# Asfaloth_L2_AVI_ver1_1.net
KiCad netlist of a schematic drawn in Altium Designer
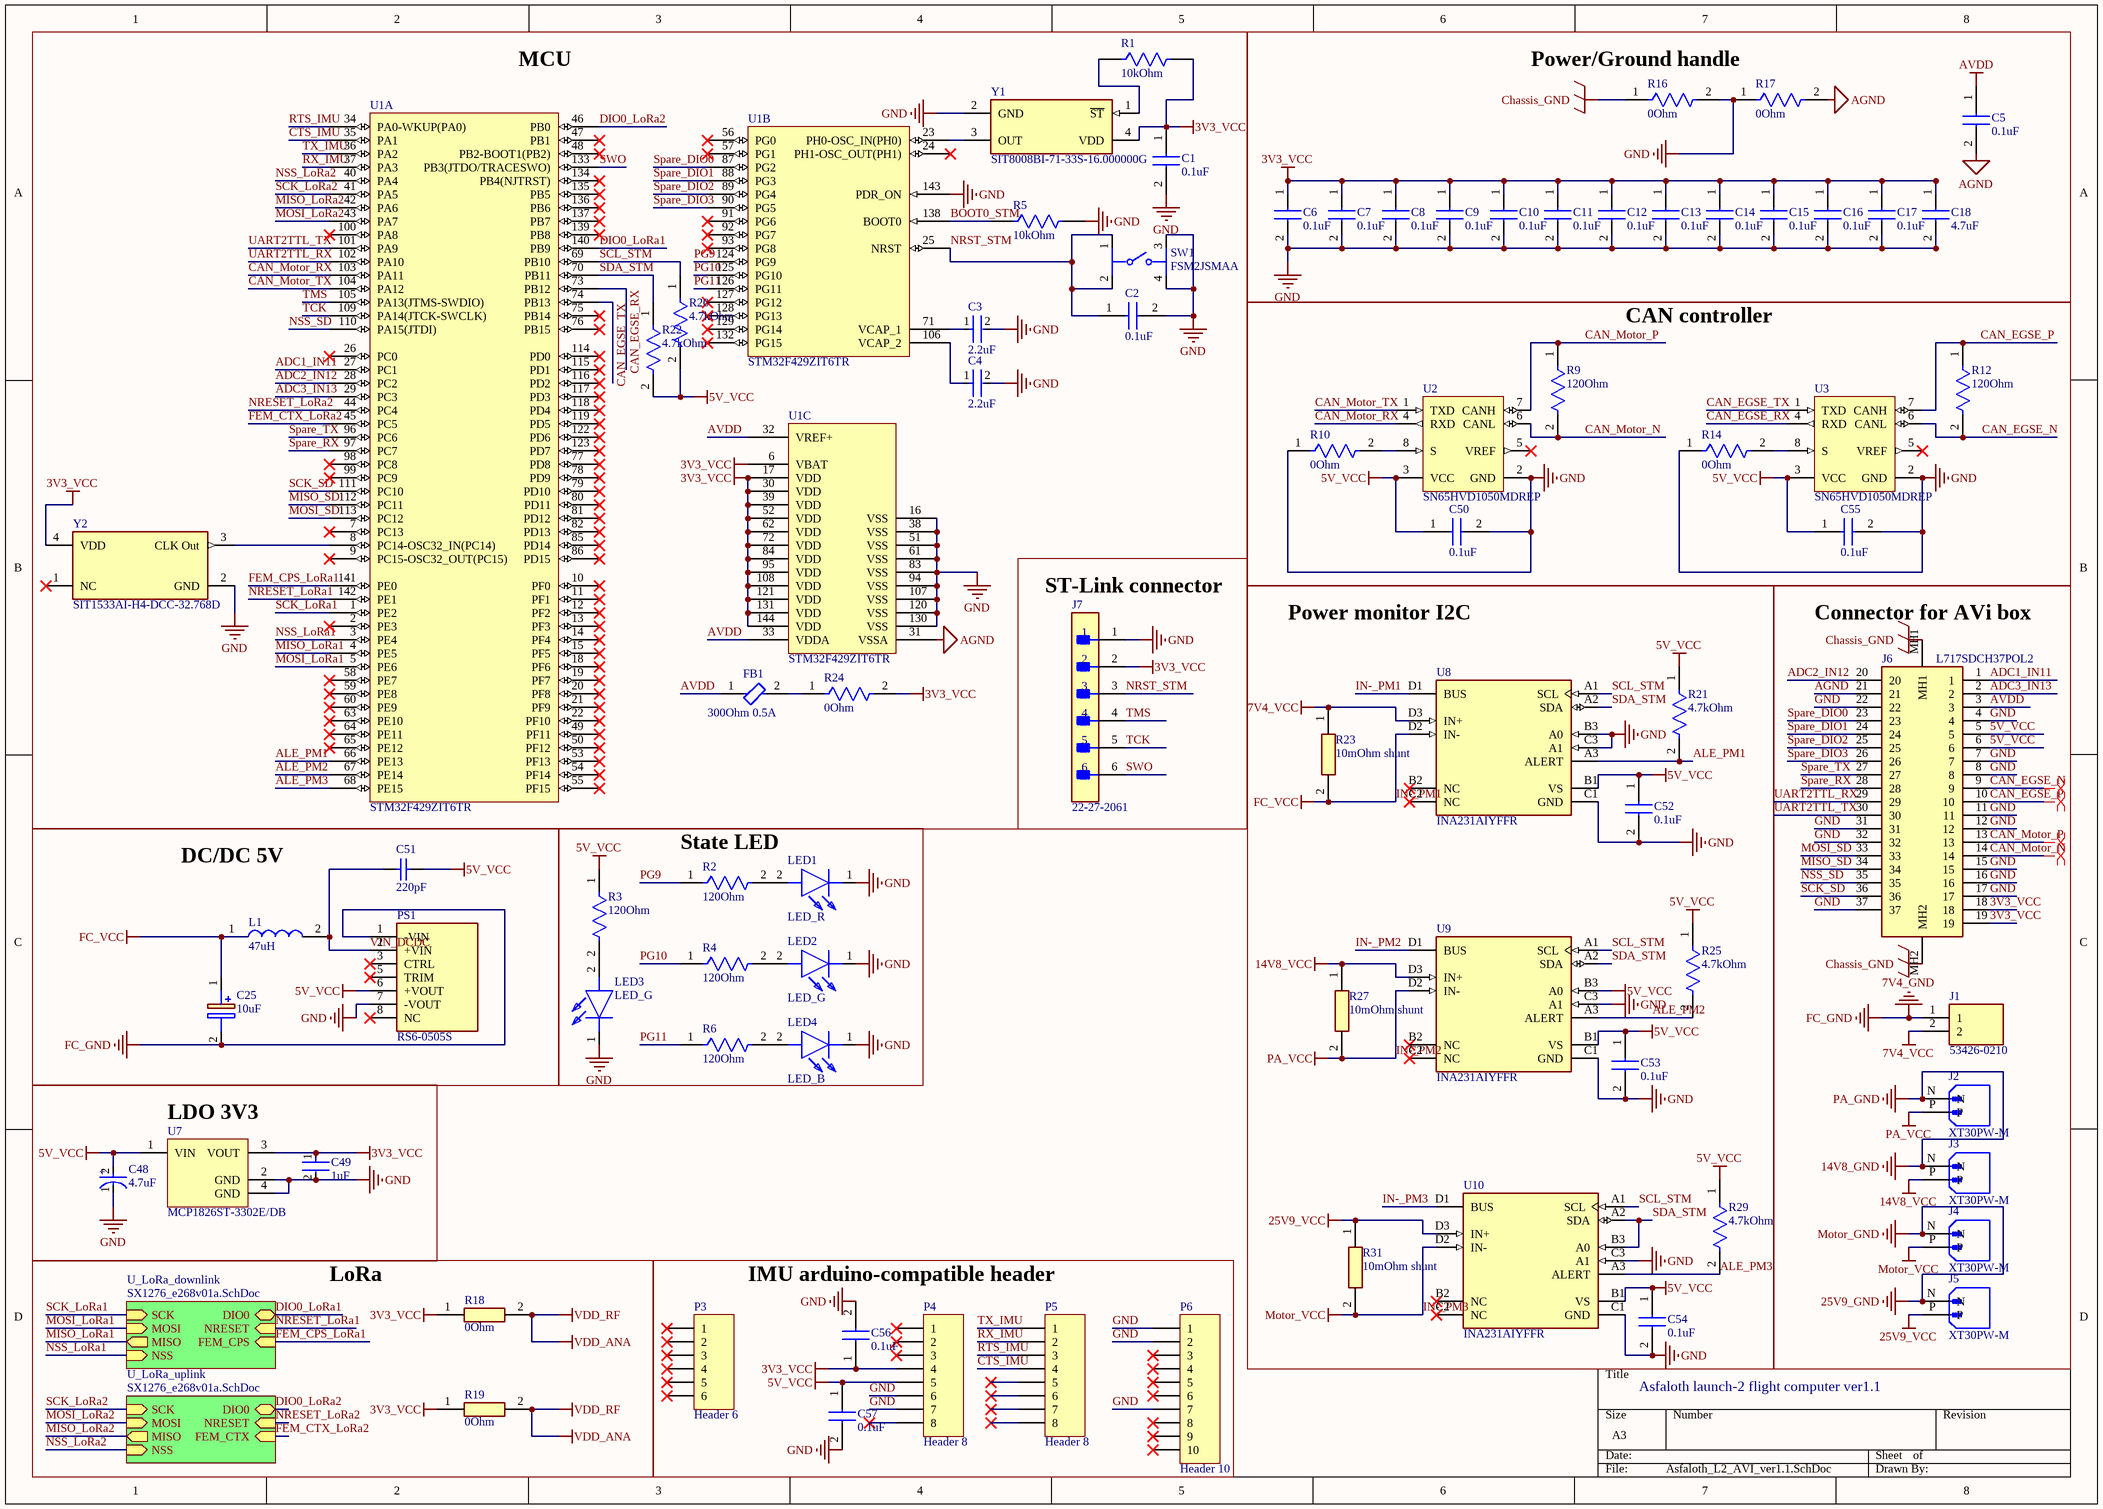
[diagram p0: Asfaloth_L2_AVI_ver1.1.SchDoc]

(export (version "E")
  (design (tool "Eeschema 10.0.6"))
  (components
    (comp (ref "C1")
      (value "0.1uF")
      (footprint "SamacSys:CAPC1608X87N")
      (description "Capacitor")
      (fields
        (field (name "MANUFACTURER_PART_NUMBER") "C0603C104J4RECAUTO")
        (field (name "MOUSER PART NUMBER") "80-C0603C104J4RECAUT")
      )
      (libsource (lib "*") (part "C0603C104J4RECAUTO"))
    )
    (comp (ref "C2")
      (value "0.1uF")
      (footprint "SamacSys:CAPC1608X87N")
      (description "Capacitor")
      (fields
        (field (name "MANUFACTURER_PART_NUMBER") "C0603C104J4RECAUTO")
        (field (name "MOUSER PART NUMBER") "80-C0603C104J4RECAUT")
      )
      (libsource (lib "*") (part "C0603C104J4RECAUTO"))
    )
    (comp (ref "C3")
      (value "2.2uF")
      (footprint "FP-GRT155-0_2-IPC_C")
      (description "Multi-Layer Ceramic Capacitor 2.2uF 10V X6S ±10% 0402 Paper T/R")
      (fields (field (name "TOLERANCE") "10%"))
      (libsource (lib "Altium Content Vault") (part "02cd4be3c70576c341d710602a673aa"))
    )
    (comp (ref "C4")
      (value "2.2uF")
      (footprint "FP-GRT155-0_2-IPC_C")
      (description "Multi-Layer Ceramic Capacitor 2.2uF 10V X6S ±10% 0402 Paper T/R")
      (fields (field (name "TOLERANCE") "10%"))
      (libsource (lib "Altium Content Vault") (part "02cd4be3c70576c341d710602a673aa"))
    )
    (comp (ref "C5")
      (value "0.1uF")
      (footprint "SamacSys:CAPC1608X87N")
      (description "Capacitor")
      (fields
        (field (name "MANUFACTURER_PART_NUMBER") "C0603C104J4RECAUTO")
        (field (name "MOUSER PART NUMBER") "80-C0603C104J4RECAUT")
      )
      (libsource (lib "*") (part "C0603C104J4RECAUTO"))
    )
    (comp (ref "C6")
      (value "0.1uF")
      (footprint "SamacSys:CAPC1608X87N")
      (description "Capacitor")
      (fields
        (field (name "MANUFACTURER_PART_NUMBER") "C0603C104J4RECAUTO")
        (field (name "MOUSER PART NUMBER") "80-C0603C104J4RECAUT")
      )
      (libsource (lib "*") (part "C0603C104J4RECAUTO"))
    )
    (comp (ref "C7")
      (value "0.1uF")
      (footprint "SamacSys:CAPC1608X87N")
      (description "Capacitor")
      (fields
        (field (name "MANUFACTURER_PART_NUMBER") "C0603C104J4RECAUTO")
        (field (name "MOUSER PART NUMBER") "80-C0603C104J4RECAUT")
      )
      (libsource (lib "*") (part "C0603C104J4RECAUTO"))
    )
    (comp (ref "C8")
      (value "0.1uF")
      (footprint "SamacSys:CAPC1608X87N")
      (description "Capacitor")
      (fields
        (field (name "MANUFACTURER_PART_NUMBER") "C0603C104J4RECAUTO")
        (field (name "MOUSER PART NUMBER") "80-C0603C104J4RECAUT")
      )
      (libsource (lib "*") (part "C0603C104J4RECAUTO"))
    )
    (comp (ref "C9")
      (value "0.1uF")
      (footprint "SamacSys:CAPC1608X87N")
      (description "Capacitor")
      (fields
        (field (name "MANUFACTURER_PART_NUMBER") "C0603C104J4RECAUTO")
        (field (name "MOUSER PART NUMBER") "80-C0603C104J4RECAUT")
      )
      (libsource (lib "*") (part "C0603C104J4RECAUTO"))
    )
    (comp (ref "C10")
      (value "0.1uF")
      (footprint "SamacSys:CAPC1608X87N")
      (description "Capacitor")
      (fields
        (field (name "MANUFACTURER_PART_NUMBER") "C0603C104J4RECAUTO")
        (field (name "MOUSER PART NUMBER") "80-C0603C104J4RECAUT")
      )
      (libsource (lib "*") (part "C0603C104J4RECAUTO"))
    )
    (comp (ref "C11")
      (value "0.1uF")
      (footprint "SamacSys:CAPC1608X87N")
      (description "Capacitor")
      (fields
        (field (name "MANUFACTURER_PART_NUMBER") "C0603C104J4RECAUTO")
        (field (name "MOUSER PART NUMBER") "80-C0603C104J4RECAUT")
      )
      (libsource (lib "*") (part "C0603C104J4RECAUTO"))
    )
    (comp (ref "C12")
      (value "0.1uF")
      (footprint "SamacSys:CAPC1608X87N")
      (description "Capacitor")
      (fields
        (field (name "MANUFACTURER_PART_NUMBER") "C0603C104J4RECAUTO")
        (field (name "MOUSER PART NUMBER") "80-C0603C104J4RECAUT")
      )
      (libsource (lib "*") (part "C0603C104J4RECAUTO"))
    )
    (comp (ref "C13")
      (value "0.1uF")
      (footprint "SamacSys:CAPC1608X87N")
      (description "Capacitor")
      (fields
        (field (name "MANUFACTURER_PART_NUMBER") "C0603C104J4RECAUTO")
        (field (name "MOUSER PART NUMBER") "80-C0603C104J4RECAUT")
      )
      (libsource (lib "*") (part "C0603C104J4RECAUTO"))
    )
    (comp (ref "C14")
      (value "0.1uF")
      (footprint "SamacSys:CAPC1608X87N")
      (description "Capacitor")
      (fields
        (field (name "MANUFACTURER_PART_NUMBER") "C0603C104J4RECAUTO")
        (field (name "MOUSER PART NUMBER") "80-C0603C104J4RECAUT")
      )
      (libsource (lib "*") (part "C0603C104J4RECAUTO"))
    )
    (comp (ref "C15")
      (value "0.1uF")
      (footprint "SamacSys:CAPC1608X87N")
      (description "Capacitor")
      (fields
        (field (name "MANUFACTURER_PART_NUMBER") "C0603C104J4RECAUTO")
        (field (name "MOUSER PART NUMBER") "80-C0603C104J4RECAUT")
      )
      (libsource (lib "*") (part "C0603C104J4RECAUTO"))
    )
    (comp (ref "C16")
      (value "0.1uF")
      (footprint "SamacSys:CAPC1608X87N")
      (description "Capacitor")
      (fields
        (field (name "MANUFACTURER_PART_NUMBER") "C0603C104J4RECAUTO")
        (field (name "MOUSER PART NUMBER") "80-C0603C104J4RECAUT")
      )
      (libsource (lib "*") (part "C0603C104J4RECAUTO"))
    )
    (comp (ref "C17")
      (value "0.1uF")
      (footprint "SamacSys:CAPC1608X87N")
      (description "Capacitor")
      (fields
        (field (name "MANUFACTURER_PART_NUMBER") "C0603C104J4RECAUTO")
        (field (name "MOUSER PART NUMBER") "80-C0603C104J4RECAUT")
      )
      (libsource (lib "*") (part "C0603C104J4RECAUTO"))
    )
    (comp (ref "C18")
      (value "4.7uF")
      (footprint "SamacSys:GRT188")
      (description "Capacitor")
      (fields
        (field (name "MANUFACTURER_PART_NUMBER") "GRT188C71C475KE13D")
        (field (name "MOUSER PART NUMBER") "81-GRT188C71C475KE13")
      )
      (libsource (lib "*") (part "GRT188C71C475KE13D"))
    )
    (comp (ref "C25")
      (value "10uF")
      (footprint "SamacSys:CAPAE830X650N")
      (description "Capacitor Polarised")
      (fields
        (field (name "MANUFACTURER_PART_NUMBER") "EEE-TG1J100P")
        (field (name "MOUSER PART NUMBER") "667-EEE-TG1J100P")
      )
      (libsource (lib "*") (part "EEE-TG1J100P"))
    )
    (comp (ref "C48")
      (value "4.7uF")
      (footprint "FP-TAJA-MFG")
      (description "4.7uF 16V  ±10% 4Ω 1206  SMD Tantalum Capacitor")
      (fields (field (name "TOLERANCE") "10%") (field (name "VOLTAGE") "16V"))
      (libsource (lib "Altium Content Vault") (part "203bc49f2ac43e59fd269a8c329ed05"))
    )
    (comp (ref "C49")
      (value "1uF")
      (footprint "FP-GCM21B-0_15-MFG")
      (description "Ceramic Capacitor for Automotive 1uF ±10% 16VDC X7R 0805 Embossed T/R")
      (fields (field (name "TOLERANCE") "10%"))
      (libsource (lib "Altium Content Vault") (part "02cd4be3c70576c341d710602a673aa"))
    )
    (comp (ref "C50")
      (value "0.1uF")
      (footprint "SamacSys:CAPC1608X87N")
      (description "Capacitor")
      (fields
        (field (name "MANUFACTURER_PART_NUMBER") "C0603C104J4RECAUTO")
        (field (name "MOUSER PART NUMBER") "80-C0603C104J4RECAUT")
      )
      (libsource (lib "*") (part "C0603C104J4RECAUTO"))
    )
    (comp (ref "C51")
      (value "220pF")
      (footprint "CAPC1608X87X35LL15T15")
      (fields (field (name "PART NUMBER") "C0603C221J5GACAUTO") (field (name "MANUFACTURER") "Kemet"))
      (libsource (lib "Altium Content Vault") (part "CAP"))
    )
    (comp (ref "C52")
      (value "0.1uF")
      (footprint "SamacSys:CAPC1608X87N")
      (description "Capacitor")
      (fields
        (field (name "MANUFACTURER_PART_NUMBER") "C0603C104J4RECAUTO")
        (field (name "MOUSER PART NUMBER") "80-C0603C104J4RECAUT")
      )
      (libsource (lib "*") (part "C0603C104J4RECAUTO"))
    )
    (comp (ref "C53")
      (value "0.1uF")
      (footprint "SamacSys:CAPC1608X87N")
      (description "Capacitor")
      (fields
        (field (name "MANUFACTURER_PART_NUMBER") "C0603C104J4RECAUTO")
        (field (name "MOUSER PART NUMBER") "80-C0603C104J4RECAUT")
      )
      (libsource (lib "*") (part "C0603C104J4RECAUTO"))
    )
    (comp (ref "C54")
      (value "0.1uF")
      (footprint "SamacSys:CAPC1608X87N")
      (description "Capacitor")
      (fields
        (field (name "MANUFACTURER_PART_NUMBER") "C0603C104J4RECAUTO")
        (field (name "MOUSER PART NUMBER") "80-C0603C104J4RECAUT")
      )
      (libsource (lib "*") (part "C0603C104J4RECAUTO"))
    )
    (comp (ref "C55")
      (value "0.1uF")
      (footprint "SamacSys:CAPC1608X87N")
      (description "Capacitor")
      (fields
        (field (name "MANUFACTURER_PART_NUMBER") "C0603C104J4RECAUTO")
        (field (name "MOUSER PART NUMBER") "80-C0603C104J4RECAUT")
      )
      (libsource (lib "*") (part "C0603C104J4RECAUTO"))
    )
    (comp (ref "C56")
      (value "0.1uF")
      (footprint "SamacSys:CAPC1608X87N")
      (description "Capacitor")
      (fields
        (field (name "MANUFACTURER_PART_NUMBER") "C0603C104J4RECAUTO")
        (field (name "MOUSER PART NUMBER") "80-C0603C104J4RECAUT")
      )
      (libsource (lib "*") (part "C0603C104J4RECAUTO"))
    )
    (comp (ref "C57")
      (value "0.1uF")
      (footprint "SamacSys:CAPC1608X87N")
      (description "Capacitor")
      (fields
        (field (name "MANUFACTURER_PART_NUMBER") "C0603C104J4RECAUTO")
        (field (name "MOUSER PART NUMBER") "80-C0603C104J4RECAUT")
      )
      (libsource (lib "*") (part "C0603C104J4RECAUTO"))
    )
    (comp (ref "FB1")
      (value "300Ohm 0.5A")
      (footprint "FP-MMZ1608-0_8-MFG")
      (description " Signal Line Ferrite Bead 300Ω  @ 100MHz 500mA DCR 300mΩ SMD 0603")
      (fields (field (name "TOLERANCE") "25%"))
      (libsource (lib "Altium Content Vault") (part "5f30dd21d616792df468990f7003faa"))
    )
    (comp (ref "J1")
      (value "53426-0210")
      (footprint "534260210")
      (description "Headers & Wire Housings 2.50MM 2P RA HDR FRCTN POS LOCK")
      (fields (field (name "MOUSER PART NUMBER") "538-53426-0210"))
      (libsource (lib "53426-0210") (part "53426-0210"))
    )
    (comp (ref "J2")
      (value "XT30PW-M")
      (footprint "AMASS_XT30PW-M")
      (description "Socket; DC supply; XT30; male; PIN: 2; on PCBs; THT; Colour: yellow")
      (fields (field (name "MF") "AMASS"))
      (libsource (lib "XT30PW-M") (part "XT30PW-M"))
    )
    (comp (ref "J3")
      (value "XT30PW-M")
      (footprint "AMASS_XT30PW-M")
      (description "Socket; DC supply; XT30; male; PIN: 2; on PCBs; THT; Colour: yellow")
      (fields (field (name "MF") "AMASS"))
      (libsource (lib "XT30PW-M") (part "XT30PW-M"))
    )
    (comp (ref "J4")
      (value "XT30PW-M")
      (footprint "AMASS_XT30PW-M")
      (description "Socket; DC supply; XT30; male; PIN: 2; on PCBs; THT; Colour: yellow")
      (fields (field (name "MF") "AMASS"))
      (libsource (lib "XT30PW-M") (part "XT30PW-M"))
    )
    (comp (ref "J5")
      (value "XT30PW-M")
      (footprint "AMASS_XT30PW-M")
      (description "Socket; DC supply; XT30; male; PIN: 2; on PCBs; THT; Colour: yellow")
      (fields (field (name "MF") "AMASS"))
      (libsource (lib "XT30PW-M") (part "XT30PW-M"))
    )
    (comp (ref "J6")
      (value "L717SDCH37POL2")
      (footprint "L717SDCH37POL2")
      (libsource (lib "L717SDCH37POL2") (part "L717SDCH37POL2"))
    )
    (comp (ref "J7")
      (value "22-27-2061")
      (footprint "FP-22-27-2061-MFG")
      (description "CONN HEADER VERT 6POS 2.54MM")
      (libsource (lib "Altium Content Vault") (part "f2cb566baf1c37ab5a3b8e90bbeafd6"))
    )
    (comp (ref "L1")
      (value "47uH")
      (footprint "SamacSys:SRR5228A")
      (description "Inductor")
      (fields
        (field (name "MANUFACTURER_PART_NUMBER") "SRR5228A-470M")
        (field (name "MOUSER PART NUMBER") "6521-SRR5228A-470M")
      )
      (libsource (lib "*") (part "SRR5228A-470M"))
    )
    (comp (ref "LED1")
      (value "LED_R")
      (footprint "SamacSys:LEDC2012X80N")
      (description "LED")
      (fields
        (field (name "MANUFACTURER_PART_NUMBER") "SML-H12V8TT86C")
        (field (name "MOUSER PART NUMBER") "755-SML-H12V8TT86C")
      )
      (libsource (lib "*") (part "SML-H12V8TT86C"))
    )
    (comp (ref "LED2")
      (value "LED_G")
      (footprint "SamacSys:LEDC2012X90N")
      (description "LED")
      (fields
        (field (name "MANUFACTURER_PART_NUMBER") "SML-H12P8TT86C")
        (field (name "MOUSER PART NUMBER") "755-SML-H12P8TT86C")
      )
      (libsource (lib "*") (part "SML-H12P8TT86C"))
    )
    (comp (ref "LED3")
      (value "LED_G")
      (footprint "SamacSys:LEDC2012X90N")
      (description "LED")
      (fields
        (field (name "MANUFACTURER_PART_NUMBER") "SML-H12P8TT86C")
        (field (name "MOUSER PART NUMBER") "755-SML-H12P8TT86C")
      )
      (libsource (lib "*") (part "SML-H12P8TT86C"))
    )
    (comp (ref "LED4")
      (value "LED_B")
      (footprint "SamacSys:LEDM2012X100N")
      (description "LED")
      (fields
        (field (name "MANUFACTURER_PART_NUMBER") "SMLMN2BCTT86C")
        (field (name "MOUSER PART NUMBER") "755-SMLMN2BCTT86C")
      )
      (libsource (lib "*") (part "SMLMN2BCTT86C"))
    )
    (comp (ref "P3")
      (value "Header 6")
      (footprint "HDR1X6")
      (description "Header, 6-Pin")
      (fields (field (name "PUBLISHER") "Altium Limited"))
      (libsource (lib "Miscellaneous Connectors") (part "Header 6"))
    )
    (comp (ref "P4")
      (value "Header 8")
      (footprint "HDR1X8")
      (description "Header, 8-Pin")
      (fields (field (name "PUBLISHER") "Altium Limited"))
      (libsource (lib "Miscellaneous Connectors") (part "Header 8"))
    )
    (comp (ref "P5")
      (value "Header 8")
      (footprint "HDR1X8")
      (description "Header, 8-Pin")
      (fields (field (name "PUBLISHER") "Altium Limited"))
      (libsource (lib "Miscellaneous Connectors") (part "Header 8"))
    )
    (comp (ref "P6")
      (value "Header 10")
      (footprint "HDR1X10")
      (description "Header, 10-Pin")
      (fields (field (name "PUBLISHER") "Altium Limited"))
      (libsource (lib "Miscellaneous Connectors") (part "Header 10"))
    )
    (comp (ref "PS1")
      (value "RS6-0505S")
      (footprint "SamacSys:RS60505S")
      (description "Power Supply")
      (fields (field (name "MOUSER PART NUMBER") "919-RS6-0505S"))
      (libsource (lib "*") (part "RS6-0505S"))
    )
    (comp (ref "R1")
      (value "10kOhm")
      (footprint "FP-CRCW0805-e3-IPC_A")
      (description "RES Thick Film, 10kΩ, 1%, 0.125W, 100ppm/°C, 0805")
      (fields (field (name "TOLERANCE") "1%"))
      (libsource (lib "") (part "1029c3af85768c4190bb7ad29bc67b5_1"))
    )
    (comp (ref "R2")
      (value "120Ohm")
      (footprint "FP-ERJ2RK-MFG")
      (description "RES SMD 120 OHM 1% 1/10W 0402")
      (fields (field (name "TOLERANCE") "1%"))
      (libsource (lib "Altium Content Vault") (part "1029c3af85768c4190bb7ad29bc67b5"))
    )
    (comp (ref "R3")
      (value "120Ohm")
      (footprint "FP-ERJ2RK-MFG")
      (description "RES SMD 120 OHM 1% 1/10W 0402")
      (fields (field (name "TOLERANCE") "1%"))
      (libsource (lib "Altium Content Vault") (part "1029c3af85768c4190bb7ad29bc67b5"))
    )
    (comp (ref "R4")
      (value "120Ohm")
      (footprint "FP-ERJ2RK-MFG")
      (description "RES SMD 120 OHM 1% 1/10W 0402")
      (fields (field (name "TOLERANCE") "1%"))
      (libsource (lib "Altium Content Vault") (part "1029c3af85768c4190bb7ad29bc67b5"))
    )
    (comp (ref "R5")
      (value "10kOhm")
      (footprint "FP-CRCW0805-e3-IPC_A")
      (description "RES Thick Film, 10kΩ, 1%, 0.125W, 100ppm/°C, 0805")
      (fields (field (name "TOLERANCE") "1%"))
      (libsource (lib "") (part "1029c3af85768c4190bb7ad29bc67b5_1"))
    )
    (comp (ref "R6")
      (value "120Ohm")
      (footprint "FP-ERJ2RK-MFG")
      (description "RES SMD 120 OHM 1% 1/10W 0402")
      (fields (field (name "TOLERANCE") "1%"))
      (libsource (lib "Altium Content Vault") (part "1029c3af85768c4190bb7ad29bc67b5"))
    )
    (comp (ref "R9")
      (value "120Ohm")
      (footprint "FP-ERJ2RK-MFG")
      (description "RES SMD 120 OHM 1% 1/10W 0402")
      (fields (field (name "TOLERANCE") "1%"))
      (libsource (lib "Altium Content Vault") (part "1029c3af85768c4190bb7ad29bc67b5"))
    )
    (comp (ref "R10")
      (value "0Ohm")
      (footprint "FP-AC0603-0_55-IPC_A")
      (description "RES SMD 0 OHM JUMPER 1/10W 0603")
      (fields (field (name "TOLERANCE") "1%"))
      (libsource (lib "Altium Content Vault") (part "1029c3af85768c4190bb7ad29bc67b5"))
    )
    (comp (ref "R12")
      (value "120Ohm")
      (footprint "FP-ERJ2RK-MFG")
      (description "RES SMD 120 OHM 1% 1/10W 0402")
      (fields (field (name "TOLERANCE") "1%"))
      (libsource (lib "Altium Content Vault") (part "1029c3af85768c4190bb7ad29bc67b5"))
    )
    (comp (ref "R14")
      (value "0Ohm")
      (footprint "FP-AC0603-0_55-IPC_A")
      (description "RES SMD 0 OHM JUMPER 1/10W 0603")
      (fields (field (name "TOLERANCE") "1%"))
      (libsource (lib "Altium Content Vault") (part "1029c3af85768c4190bb7ad29bc67b5"))
    )
    (comp (ref "R16")
      (value "0Ohm")
      (footprint "FP-AC0603-0_55-IPC_A")
      (description "RES SMD 0 OHM JUMPER 1/10W 0603")
      (fields (field (name "TOLERANCE") "1%"))
      (libsource (lib "Altium Content Vault") (part "1029c3af85768c4190bb7ad29bc67b5"))
    )
    (comp (ref "R17")
      (value "0Ohm")
      (footprint "FP-AC0603-0_55-IPC_A")
      (description "RES SMD 0 OHM JUMPER 1/10W 0603")
      (fields (field (name "TOLERANCE") "1%"))
      (libsource (lib "Altium Content Vault") (part "1029c3af85768c4190bb7ad29bc67b5"))
    )
    (comp (ref "R18")
      (value "0Ohm")
      (footprint "SamacSys:RESC3216X60N")
      (description "Resistor")
      (fields
        (field (name "MANUFACTURER_PART_NUMBER") "RCA12060000ZSEA")
        (field (name "MOUSER PART NUMBER") "71-RCA12060000ZSEA")
      )
      (libsource (lib "*") (part "RCA12060000ZSEA"))
    )
    (comp (ref "R19")
      (value "0Ohm")
      (footprint "SamacSys:RESC3216X60N")
      (description "Resistor")
      (fields
        (field (name "MANUFACTURER_PART_NUMBER") "RCA12060000ZSEA")
        (field (name "MOUSER PART NUMBER") "71-RCA12060000ZSEA")
      )
      (libsource (lib "*") (part "RCA12060000ZSEA"))
    )
    (comp (ref "R20")
      (value "4.7kOhm")
      (footprint "FP-KTR03-IPC_C")
      (description "Res Thick Film 0603 4.7kΩ 5% 0.1W ±200ppm/°C Automotive Paper T/R")
      (fields (field (name "TOLERANCE") "5%"))
      (libsource (lib "Altium Content Vault") (part "1029c3af85768c4190bb7ad29bc67b5"))
    )
    (comp (ref "R21")
      (value "4.7kOhm")
      (footprint "FP-KTR03-IPC_C")
      (description "Res Thick Film 0603 4.7kΩ 5% 0.1W ±200ppm/°C Automotive Paper T/R")
      (fields (field (name "TOLERANCE") "5%"))
      (libsource (lib "Altium Content Vault") (part "1029c3af85768c4190bb7ad29bc67b5"))
    )
    (comp (ref "R22")
      (value "4.7kOhm")
      (footprint "FP-KTR03-IPC_C")
      (description "Res Thick Film 0603 4.7kΩ 5% 0.1W ±200ppm/°C Automotive Paper T/R")
      (fields (field (name "TOLERANCE") "5%"))
      (libsource (lib "Altium Content Vault") (part "1029c3af85768c4190bb7ad29bc67b5"))
    )
    (comp (ref "R23")
      (value "10mOhm shunt")
      (footprint "SamacSys:CSS0805FT10L0")
      (description "Resistor")
      (fields
        (field (name "MANUFACTURER_PART_NUMBER") "CSS0805FT10L0")
        (field (name "MOUSER PART NUMBER") "708-CSS0805FT10L0")
      )
      (libsource (lib "*") (part "CSS0805FT10L0"))
    )
    (comp (ref "R24")
      (value "0Ohm")
      (footprint "FP-AC0603-0_55-IPC_A")
      (description "RES SMD 0 OHM JUMPER 1/10W 0603")
      (fields (field (name "TOLERANCE") "1%"))
      (libsource (lib "Altium Content Vault") (part "1029c3af85768c4190bb7ad29bc67b5"))
    )
    (comp (ref "R25")
      (value "4.7kOhm")
      (footprint "FP-KTR03-IPC_C")
      (description "Res Thick Film 0603 4.7kΩ 5% 0.1W ±200ppm/°C Automotive Paper T/R")
      (fields (field (name "TOLERANCE") "5%"))
      (libsource (lib "Altium Content Vault") (part "1029c3af85768c4190bb7ad29bc67b5"))
    )
    (comp (ref "R27")
      (value "10mOhm shunt")
      (footprint "SamacSys:CSS0805FT10L0")
      (description "Resistor")
      (fields
        (field (name "MANUFACTURER_PART_NUMBER") "CSS0805FT10L0")
        (field (name "MOUSER PART NUMBER") "708-CSS0805FT10L0")
      )
      (libsource (lib "*") (part "CSS0805FT10L0"))
    )
    (comp (ref "R29")
      (value "4.7kOhm")
      (footprint "FP-KTR03-IPC_C")
      (description "Res Thick Film 0603 4.7kΩ 5% 0.1W ±200ppm/°C Automotive Paper T/R")
      (fields (field (name "TOLERANCE") "5%"))
      (libsource (lib "Altium Content Vault") (part "1029c3af85768c4190bb7ad29bc67b5"))
    )
    (comp (ref "R31")
      (value "10mOhm shunt")
      (footprint "SamacSys:CSS0805FT10L0")
      (description "Resistor")
      (fields
        (field (name "MANUFACTURER_PART_NUMBER") "CSS0805FT10L0")
        (field (name "MOUSER PART NUMBER") "708-CSS0805FT10L0")
      )
      (libsource (lib "*") (part "CSS0805FT10L0"))
    )
    (comp (ref "SW1")
      (value "FSM2JSMAA")
      (footprint "FP-FSM2JSMAA-MFG")
      (description "SWITCH TACTILE SPST-NO 0.05A 24V")
      (fields
        (field (name "MANUFACTURER") "TE Connectivity")
        (field (name "OCTOPART") "https://octopart.com/fsm2jsmaa-te+connectivity-41720620")
      )
      (libsource (lib "Altium Content Vault") (part "b8895f3f4cefb76e1819d2863dba89b"))
    )
    (comp (ref "U1")
      (value "STM32F429ZIT6TR")
      (footprint "STM-LQFP144_M")
      (libsource (lib "Altium Content Vault") (part "MC-ARM-STM32F4X7_9-LQFP144"))
    )
    (comp (ref "U2")
      (value "SN65HVD1050MDREP")
      (footprint "D0008A_M")
      (fields (field (name "MANUFACTURER") "Texas Instruments"))
      (libsource (lib "Altium Content Vault") (part "TI-SN65HVD1050-EP-SOIC_D-8"))
    )
    (comp (ref "U3")
      (value "SN65HVD1050MDREP")
      (footprint "D0008A_M")
      (fields (field (name "MANUFACTURER") "Texas Instruments"))
      (libsource (lib "Altium Content Vault") (part "TI-SN65HVD1050-EP-SOIC_D-8"))
    )
    (comp (ref "U7")
      (value "MCP1826ST-3302E/DB")
      (footprint "SOT-223-DB3_L")
      (libsource (lib "Altium Content Vault") (part "PM-LINEREG-MCP1826-IL4"))
    )
    (comp (ref "U8")
      (value "INA231AIYFFR")
      (footprint "FP-YFF0012-IPC_C")
      (description "IC CURRENT MONITOR 100DB 12DSBGA")
      (libsource (lib "Altium Content Vault") (part "45ec0a68ca5e232ea1aa11670bcc384"))
    )
    (comp (ref "U9")
      (value "INA231AIYFFR")
      (footprint "FP-YFF0012-IPC_C")
      (description "IC CURRENT MONITOR 100DB 12DSBGA")
      (libsource (lib "Altium Content Vault") (part "45ec0a68ca5e232ea1aa11670bcc384"))
    )
    (comp (ref "U10")
      (value "INA231AIYFFR")
      (footprint "FP-YFF0012-IPC_C")
      (description "IC CURRENT MONITOR 100DB 12DSBGA")
      (libsource (lib "Altium Content Vault") (part "45ec0a68ca5e232ea1aa11670bcc384"))
    )
    (comp (ref "Y1")
      (value "SIT8008BI-71-33S-16.000000G")
      (footprint "FP-SiT8008-7-MFG")
      (description "MEMS OSC XO 16.0000MHZ H/LV-CMOS")
      (libsource (lib "Altium Content Vault") (part "0b6e30c8c84b5cf713c4e00c700effb"))
    )
    (comp (ref "Y2")
      (value "SIT1533AI-H4-DCC-32.768D")
      (footprint "FP-SiT1533-H-MFG")
      (description "MEMS OSC XO 32.7680KHZ LVCMOS")
      (libsource (lib "Altium Content Vault") (part "d6da4f2ecb1e1a500d17fb349569450"))
    )
  )
  (nets
    (net (code "1") (name "/ADC1_IN11") (class "Default")
      (node (ref "J6") (pin "1") (pinfunction "1_1") (pintype "passive"))
      (node (ref "U1") (pin "27") (pinfunction "PC1_27") (pintype "bidirectional"))
    )
    (net (code "2") (name "/ADC2_IN12") (class "Default")
      (node (ref "J6") (pin "20") (pinfunction "20_20") (pintype "passive"))
      (node (ref "U1") (pin "28") (pinfunction "PC2_28") (pintype "bidirectional"))
    )
    (net (code "3") (name "/ADC3_IN13") (class "Default")
      (node (ref "J6") (pin "2") (pinfunction "2_2") (pintype "passive"))
      (node (ref "U1") (pin "29") (pinfunction "PC3_29") (pintype "bidirectional"))
    )
    (net (code "4") (name "/ALE_PM1") (class "Default")
      (node (ref "R21") (pin "2") (pinfunction "2_2") (pintype "passive"))
      (node (ref "U1") (pin "66") (pinfunction "PE13_66") (pintype "bidirectional"))
      (node (ref "U8") (pin "A3") (pinfunction "ALERT_A3") (pintype "open_collector"))
    )
    (net (code "5") (name "/ALE_PM2") (class "Default")
      (node (ref "R25") (pin "2") (pinfunction "2_2") (pintype "passive"))
      (node (ref "U1") (pin "67") (pinfunction "PE14_67") (pintype "bidirectional"))
      (node (ref "U9") (pin "A3") (pinfunction "ALERT_A3") (pintype "open_collector"))
    )
    (net (code "6") (name "/ALE_PM3") (class "Default")
      (node (ref "R29") (pin "2") (pinfunction "2_2") (pintype "passive"))
      (node (ref "U1") (pin "68") (pinfunction "PE15_68") (pintype "bidirectional"))
      (node (ref "U10") (pin "A3") (pinfunction "ALERT_A3") (pintype "open_collector"))
    )
    (net (code "7") (name "/BOOT0_STM") (class "Default")
      (node (ref "R5") (pin "1") (pinfunction "1_1") (pintype "passive"))
      (node (ref "U1") (pin "138") (pinfunction "BOOT0_138") (pintype "input"))
    )
    (net (code "8") (name "/CAN_EGSE_N") (class "Default")
      (node (ref "J6") (pin "9") (pinfunction "9_9") (pintype "passive"))
      (node (ref "R12") (pin "2") (pinfunction "2_2") (pintype "passive"))
      (node (ref "U3") (pin "6") (pinfunction "CANL_6") (pintype "bidirectional"))
    )
    (net (code "9") (name "/CAN_EGSE_P") (class "Default")
      (node (ref "J6") (pin "10") (pinfunction "10_10") (pintype "passive"))
      (node (ref "R12") (pin "1") (pinfunction "1_1") (pintype "passive"))
      (node (ref "U3") (pin "7") (pinfunction "CANH_7") (pintype "bidirectional"))
    )
    (net (code "10") (name "/CAN_EGSE_RX") (class "Default")
      (node (ref "U1") (pin "73") (pinfunction "PB12_73") (pintype "bidirectional"))
      (node (ref "U3") (pin "4") (pinfunction "RXD_4") (pintype "output"))
    )
    (net (code "11") (name "/CAN_EGSE_TX") (class "Default")
      (node (ref "U1") (pin "74") (pinfunction "PB13_74") (pintype "bidirectional"))
      (node (ref "U3") (pin "1") (pinfunction "TXD_1") (pintype "input"))
    )
    (net (code "12") (name "/CAN_Motor_N") (class "Default")
      (node (ref "J6") (pin "14") (pinfunction "14_14") (pintype "passive"))
      (node (ref "R9") (pin "2") (pinfunction "2_2") (pintype "passive"))
      (node (ref "U2") (pin "6") (pinfunction "CANL_6") (pintype "bidirectional"))
    )
    (net (code "13") (name "/CAN_Motor_P") (class "Default")
      (node (ref "J6") (pin "13") (pinfunction "13_13") (pintype "passive"))
      (node (ref "R9") (pin "1") (pinfunction "1_1") (pintype "passive"))
      (node (ref "U2") (pin "7") (pinfunction "CANH_7") (pintype "bidirectional"))
    )
    (net (code "14") (name "/CAN_Motor_RX") (class "Default")
      (node (ref "U1") (pin "103") (pinfunction "PA11_103") (pintype "bidirectional"))
      (node (ref "U2") (pin "4") (pinfunction "RXD_4") (pintype "output"))
    )
    (net (code "15") (name "/CAN_Motor_TX") (class "Default")
      (node (ref "U1") (pin "104") (pinfunction "PA12_104") (pintype "bidirectional"))
      (node (ref "U2") (pin "1") (pinfunction "TXD_1") (pintype "input"))
    )
    (net (code "16") (name "/CTS_IMU") (class "Default")
      (node (ref "P5") (pin "4") (pinfunction "4_4") (pintype "passive"))
      (node (ref "U1") (pin "35") (pinfunction "PA1_35") (pintype "bidirectional"))
    )
    (net (code "17") (name "/DIO0_LoRa1") (class "Default")
      (node (ref "U1") (pin "140") (pinfunction "PB9_140") (pintype "bidirectional"))
    )
    (net (code "18") (name "/DIO0_LoRa2") (class "Default")
      (node (ref "U1") (pin "46") (pinfunction "PB0_46") (pintype "bidirectional"))
    )
    (net (code "19") (name "/FEM_CPS_LoRa1") (class "Default")
      (node (ref "U1") (pin "141") (pinfunction "PE0_141") (pintype "bidirectional"))
    )
    (net (code "20") (name "/FEM_CTX_LoRa2") (class "Default")
      (node (ref "U1") (pin "45") (pinfunction "PC5_45") (pintype "bidirectional"))
    )
    (net (code "21") (name "/MISO_LoRa1") (class "Default")
      (node (ref "U1") (pin "4") (pinfunction "PE5_4") (pintype "bidirectional"))
    )
    (net (code "22") (name "/MISO_LoRa2") (class "Default")
      (node (ref "U1") (pin "42") (pinfunction "PA6_42") (pintype "bidirectional"))
    )
    (net (code "23") (name "/MISO_SD") (class "Default")
      (node (ref "J6") (pin "34") (pinfunction "34_34") (pintype "passive"))
      (node (ref "U1") (pin "112") (pinfunction "PC11_112") (pintype "bidirectional"))
    )
    (net (code "24") (name "/MOSI_LoRa1") (class "Default")
      (node (ref "U1") (pin "5") (pinfunction "PE6_5") (pintype "bidirectional"))
    )
    (net (code "25") (name "/MOSI_LoRa2") (class "Default")
      (node (ref "U1") (pin "43") (pinfunction "PA7_43") (pintype "bidirectional"))
    )
    (net (code "26") (name "/MOSI_SD") (class "Default")
      (node (ref "J6") (pin "33") (pinfunction "33_33") (pintype "passive"))
      (node (ref "U1") (pin "113") (pinfunction "PC12_113") (pintype "bidirectional"))
    )
    (net (code "27") (name "/NRESET_LoRa1") (class "Default")
      (node (ref "U1") (pin "142") (pinfunction "PE1_142") (pintype "bidirectional"))
    )
    (net (code "28") (name "/NRESET_LoRa2") (class "Default")
      (node (ref "U1") (pin "44") (pinfunction "PC4_44") (pintype "bidirectional"))
    )
    (net (code "29") (name "/NRST_STM") (class "Default")
      (node (ref "C2") (pin "1") (pinfunction "1_1") (pintype "passive"))
      (node (ref "J7") (pin "3") (pinfunction "3_3") (pintype "passive"))
      (node (ref "SW1") (pin "1") (pinfunction "1_1") (pintype "passive"))
      (node (ref "SW1") (pin "2") (pinfunction "2_2") (pintype "passive"))
      (node (ref "U1") (pin "25") (pinfunction "NRST_25") (pintype "bidirectional"))
    )
    (net (code "30") (name "/NSS_LoRa1") (class "Default")
      (node (ref "U1") (pin "3") (pinfunction "PE4_3") (pintype "bidirectional"))
    )
    (net (code "31") (name "/NSS_LoRa2") (class "Default")
      (node (ref "U1") (pin "40") (pinfunction "PA4_40") (pintype "bidirectional"))
    )
    (net (code "32") (name "/NSS_SD") (class "Default")
      (node (ref "J6") (pin "35") (pinfunction "35_35") (pintype "passive"))
      (node (ref "U1") (pin "110") (pinfunction "PA15(JTDI)_110") (pintype "bidirectional"))
    )
    (net (code "33") (name "/PG9") (class "Default")
      (node (ref "R2") (pin "1") (pinfunction "1_1") (pintype "passive"))
      (node (ref "U1") (pin "124") (pinfunction "PG9_124") (pintype "bidirectional"))
    )
    (net (code "34") (name "/PG10") (class "Default")
      (node (ref "R4") (pin "1") (pinfunction "1_1") (pintype "passive"))
      (node (ref "U1") (pin "125") (pinfunction "PG10_125") (pintype "bidirectional"))
    )
    (net (code "35") (name "/PG11") (class "Default")
      (node (ref "R6") (pin "1") (pinfunction "1_1") (pintype "passive"))
      (node (ref "U1") (pin "126") (pinfunction "PG11_126") (pintype "bidirectional"))
    )
    (net (code "36") (name "/RTS_IMU") (class "Default")
      (node (ref "P5") (pin "3") (pinfunction "3_3") (pintype "passive"))
      (node (ref "U1") (pin "34") (pinfunction "PA0-WKUP(PA0)_34") (pintype "bidirectional"))
    )
    (net (code "37") (name "/RX_IMU") (class "Default")
      (node (ref "P5") (pin "2") (pinfunction "2_2") (pintype "passive"))
      (node (ref "U1") (pin "37") (pinfunction "PA3_37") (pintype "bidirectional"))
    )
    (net (code "38") (name "/SCK_LoRa1") (class "Default")
      (node (ref "U1") (pin "1") (pinfunction "PE2_1") (pintype "bidirectional"))
    )
    (net (code "39") (name "/SCK_LoRa2") (class "Default")
      (node (ref "U1") (pin "41") (pinfunction "PA5_41") (pintype "bidirectional"))
    )
    (net (code "40") (name "/SCK_SD") (class "Default")
      (node (ref "J6") (pin "36") (pinfunction "36_36") (pintype "passive"))
      (node (ref "U1") (pin "111") (pinfunction "PC10_111") (pintype "bidirectional"))
    )
    (net (code "41") (name "/SCL_STM") (class "Default")
      (node (ref "R20") (pin "1") (pinfunction "1_1") (pintype "passive"))
      (node (ref "U1") (pin "69") (pinfunction "PB10_69") (pintype "bidirectional"))
      (node (ref "U10") (pin "A1") (pinfunction "SCL_A1") (pintype "input"))
      (node (ref "U8") (pin "A1") (pinfunction "SCL_A1") (pintype "input"))
      (node (ref "U9") (pin "A1") (pinfunction "SCL_A1") (pintype "input"))
    )
    (net (code "42") (name "/SDA_STM") (class "Default")
      (node (ref "R22") (pin "1") (pinfunction "1_1") (pintype "passive"))
      (node (ref "U1") (pin "70") (pinfunction "PB11_70") (pintype "bidirectional"))
      (node (ref "U10") (pin "A2") (pinfunction "SDA_A2") (pintype "bidirectional"))
      (node (ref "U10") (pin "B3") (pinfunction "A0_B3") (pintype "input"))
      (node (ref "U8") (pin "A2") (pinfunction "SDA_A2") (pintype "bidirectional"))
      (node (ref "U9") (pin "A2") (pinfunction "SDA_A2") (pintype "bidirectional"))
    )
    (net (code "43") (name "/SWO") (class "Default")
      (node (ref "J7") (pin "6") (pinfunction "6_6") (pintype "passive"))
      (node (ref "U1") (pin "133") (pinfunction "PB3(JTDO/TRACESWO)_133") (pintype "bidirectional"))
    )
    (net (code "44") (name "/Spare_DIO0") (class "Default")
      (node (ref "J6") (pin "23") (pinfunction "23_23") (pintype "passive"))
      (node (ref "U1") (pin "87") (pinfunction "PG2_87") (pintype "bidirectional"))
    )
    (net (code "45") (name "/Spare_DIO1") (class "Default")
      (node (ref "J6") (pin "24") (pinfunction "24_24") (pintype "passive"))
      (node (ref "U1") (pin "88") (pinfunction "PG3_88") (pintype "bidirectional"))
    )
    (net (code "46") (name "/Spare_DIO2") (class "Default")
      (node (ref "J6") (pin "25") (pinfunction "25_25") (pintype "passive"))
      (node (ref "U1") (pin "89") (pinfunction "PG4_89") (pintype "bidirectional"))
    )
    (net (code "47") (name "/Spare_DIO3") (class "Default")
      (node (ref "J6") (pin "26") (pinfunction "26_26") (pintype "passive"))
      (node (ref "U1") (pin "90") (pinfunction "PG5_90") (pintype "bidirectional"))
    )
    (net (code "48") (name "/Spare_RX") (class "Default")
      (node (ref "J6") (pin "28") (pinfunction "28_28") (pintype "passive"))
      (node (ref "U1") (pin "97") (pinfunction "PC7_97") (pintype "bidirectional"))
    )
    (net (code "49") (name "/Spare_TX") (class "Default")
      (node (ref "J6") (pin "27") (pinfunction "27_27") (pintype "passive"))
      (node (ref "U1") (pin "96") (pinfunction "PC6_96") (pintype "bidirectional"))
    )
    (net (code "50") (name "/TCK") (class "Default")
      (node (ref "J7") (pin "5") (pinfunction "5_5") (pintype "passive"))
      (node (ref "U1") (pin "109") (pinfunction "PA14(JTCK-SWCLK)_109") (pintype "bidirectional"))
    )
    (net (code "51") (name "/TMS") (class "Default")
      (node (ref "J7") (pin "4") (pinfunction "4_4") (pintype "passive"))
      (node (ref "U1") (pin "105") (pinfunction "PA13(JTMS-SWDIO)_105") (pintype "bidirectional"))
    )
    (net (code "52") (name "/TX_IMU") (class "Default")
      (node (ref "P5") (pin "1") (pinfunction "1_1") (pintype "passive"))
      (node (ref "U1") (pin "36") (pinfunction "PA2_36") (pintype "bidirectional"))
    )
    (net (code "53") (name "/UART2TTL_RX") (class "Default")
      (node (ref "J6") (pin "29") (pinfunction "29_29") (pintype "passive"))
      (node (ref "U1") (pin "102") (pinfunction "PA10_102") (pintype "bidirectional"))
    )
    (net (code "54") (name "/UART2TTL_TX") (class "Default")
      (node (ref "J6") (pin "30") (pinfunction "30_30") (pintype "passive"))
      (node (ref "U1") (pin "101") (pinfunction "PA9_101") (pintype "bidirectional"))
    )
    (net (code "55") (name "/VIN_DCDC") (class "Default")
      (node (ref "C51") (pin "1") (pinfunction "1_1") (pintype "passive"))
      (node (ref "L1") (pin "2") (pinfunction "2_2") (pintype "passive"))
      (node (ref "PS1") (pin "2") (pinfunction "+VIN_2") (pintype "passive"))
    )
    (net (code "56") (name "3V3_VCC") (class "Default")
      (node (ref "C1") (pin "1") (pinfunction "1_1") (pintype "passive"))
      (node (ref "C10") (pin "1") (pinfunction "1_1") (pintype "passive"))
      (node (ref "C11") (pin "1") (pinfunction "1_1") (pintype "passive"))
      (node (ref "C12") (pin "1") (pinfunction "1_1") (pintype "passive"))
      (node (ref "C13") (pin "1") (pinfunction "1_1") (pintype "passive"))
      (node (ref "C14") (pin "1") (pinfunction "1_1") (pintype "passive"))
      (node (ref "C15") (pin "1") (pinfunction "1_1") (pintype "passive"))
      (node (ref "C16") (pin "1") (pinfunction "1_1") (pintype "passive"))
      (node (ref "C17") (pin "1") (pinfunction "1_1") (pintype "passive"))
      (node (ref "C18") (pin "1") (pinfunction "1_1") (pintype "passive"))
      (node (ref "C49") (pin "1") (pinfunction "1_1") (pintype "passive"))
      (node (ref "C56") (pin "1") (pinfunction "1_1") (pintype "passive"))
      (node (ref "C6") (pin "1") (pinfunction "1_1") (pintype "passive"))
      (node (ref "C7") (pin "1") (pinfunction "1_1") (pintype "passive"))
      (node (ref "C8") (pin "1") (pinfunction "1_1") (pintype "passive"))
      (node (ref "C9") (pin "1") (pinfunction "1_1") (pintype "passive"))
      (node (ref "J6") (pin "18") (pinfunction "18_18") (pintype "passive"))
      (node (ref "J6") (pin "19") (pinfunction "19_19") (pintype "passive"))
      (node (ref "J7") (pin "2") (pinfunction "2_2") (pintype "passive"))
      (node (ref "P4") (pin "4") (pinfunction "4_4") (pintype "passive"))
      (node (ref "R1") (pin "2") (pinfunction "2_2") (pintype "passive"))
      (node (ref "R18") (pin "1") (pinfunction "1_1") (pintype "passive"))
      (node (ref "R19") (pin "1") (pinfunction "1_1") (pintype "passive"))
      (node (ref "R24") (pin "2") (pinfunction "2_2") (pintype "passive"))
      (node (ref "U1") (pin "108") (pinfunction "VDD_108") (pintype "power_in"))
      (node (ref "U1") (pin "121") (pinfunction "VDD_121") (pintype "power_in"))
      (node (ref "U1") (pin "131") (pinfunction "VDD_131") (pintype "power_in"))
      (node (ref "U1") (pin "144") (pinfunction "VDD_144") (pintype "power_in"))
      (node (ref "U1") (pin "17") (pinfunction "VDD_17") (pintype "power_in"))
      (node (ref "U1") (pin "30") (pinfunction "VDD_30") (pintype "power_in"))
      (node (ref "U1") (pin "39") (pinfunction "VDD_39") (pintype "power_in"))
      (node (ref "U1") (pin "52") (pinfunction "VDD_52") (pintype "power_in"))
      (node (ref "U1") (pin "6") (pinfunction "VBAT_6") (pintype "power_in"))
      (node (ref "U1") (pin "62") (pinfunction "VDD_62") (pintype "power_in"))
      (node (ref "U1") (pin "72") (pinfunction "VDD_72") (pintype "power_in"))
      (node (ref "U1") (pin "84") (pinfunction "VDD_84") (pintype "power_in"))
      (node (ref "U1") (pin "95") (pinfunction "VDD_95") (pintype "power_in"))
      (node (ref "U7") (pin "3") (pinfunction "VOUT_3") (pintype "power_in"))
      (node (ref "Y1") (pin "4") (pinfunction "VDD_4") (pintype "power_in"))
      (node (ref "Y2") (pin "4") (pinfunction "VDD_4") (pintype "power_in"))
    )
    (net (code "57") (name "5V_VCC") (class "Default")
      (node (ref "C48") (pin "2") (pinfunction "A_2") (pintype "passive"))
      (node (ref "C50") (pin "1") (pinfunction "1_1") (pintype "passive"))
      (node (ref "C51") (pin "2") (pinfunction "2_2") (pintype "passive"))
      (node (ref "C52") (pin "1") (pinfunction "1_1") (pintype "passive"))
      (node (ref "C53") (pin "1") (pinfunction "1_1") (pintype "passive"))
      (node (ref "C54") (pin "1") (pinfunction "1_1") (pintype "passive"))
      (node (ref "C55") (pin "1") (pinfunction "1_1") (pintype "passive"))
      (node (ref "C57") (pin "1") (pinfunction "1_1") (pintype "passive"))
      (node (ref "J6") (pin "5") (pinfunction "5_5") (pintype "passive"))
      (node (ref "J6") (pin "6") (pinfunction "6_6") (pintype "passive"))
      (node (ref "P4") (pin "5") (pinfunction "5_5") (pintype "passive"))
      (node (ref "PS1") (pin "6") (pinfunction "+VOUT_6") (pintype "passive"))
      (node (ref "R20") (pin "2") (pinfunction "2_2") (pintype "passive"))
      (node (ref "R21") (pin "1") (pinfunction "1_1") (pintype "passive"))
      (node (ref "R22") (pin "2") (pinfunction "2_2") (pintype "passive"))
      (node (ref "R25") (pin "1") (pinfunction "1_1") (pintype "passive"))
      (node (ref "R29") (pin "1") (pinfunction "1_1") (pintype "passive"))
      (node (ref "R3") (pin "1") (pinfunction "1_1") (pintype "passive"))
      (node (ref "U10") (pin "B1") (pinfunction "VS_B1") (pintype "power_in"))
      (node (ref "U2") (pin "3") (pinfunction "VCC_3") (pintype "power_in"))
      (node (ref "U3") (pin "3") (pinfunction "VCC_3") (pintype "power_in"))
      (node (ref "U7") (pin "1") (pinfunction "VIN_1") (pintype "power_in"))
      (node (ref "U8") (pin "B1") (pinfunction "VS_B1") (pintype "power_in"))
      (node (ref "U9") (pin "B1") (pinfunction "VS_B1") (pintype "power_in"))
      (node (ref "U9") (pin "B3") (pinfunction "A0_B3") (pintype "input"))
    )
    (net (code "58") (name "7V4_GND") (class "Default")
      (node (ref "C25") (pin "2") (pinfunction "-_2") (pintype "passive"))
      (node (ref "J1") (pin "1") (pinfunction "1_1") (pintype "passive"))
      (node (ref "PS1") (pin "1") (pinfunction "-VIN_1") (pintype "passive"))
    )
    (net (code "59") (name "7V4_VCC") (class "Default")
      (node (ref "J1") (pin "2") (pinfunction "2_2") (pintype "passive"))
      (node (ref "R23") (pin "1") (pinfunction "1_1") (pintype "passive"))
      (node (ref "U8") (pin "D3") (pinfunction "IN+_D3") (pintype "input"))
    )
    (net (code "60") (name "14V8_GND") (class "Default")
      (node (ref "J2") (pin "N") (pinfunction "N_N") (pintype "power_in"))
      (node (ref "J3") (pin "N") (pinfunction "N_N") (pintype "power_in"))
    )
    (net (code "61") (name "14V8_VCC") (class "Default")
      (node (ref "J3") (pin "P") (pinfunction "P_P") (pintype "power_in"))
      (node (ref "R27") (pin "1") (pinfunction "1_1") (pintype "passive"))
      (node (ref "U9") (pin "D3") (pinfunction "IN+_D3") (pintype "input"))
    )
    (net (code "62") (name "25V9_GND") (class "Default")
      (node (ref "J4") (pin "N") (pinfunction "N_N") (pintype "power_in"))
      (node (ref "J5") (pin "N") (pinfunction "N_N") (pintype "power_in"))
    )
    (net (code "63") (name "25V9_VCC") (class "Default")
      (node (ref "J5") (pin "P") (pinfunction "P_P") (pintype "power_in"))
      (node (ref "R31") (pin "1") (pinfunction "1_1") (pintype "passive"))
      (node (ref "U10") (pin "D3") (pinfunction "IN+_D3") (pintype "input"))
    )
    (net (code "64") (name "AGND") (class "Default")
      (node (ref "C5") (pin "2") (pinfunction "2_2") (pintype "passive"))
      (node (ref "J6") (pin "21") (pinfunction "21_21") (pintype "passive"))
      (node (ref "R17") (pin "2") (pinfunction "2_2") (pintype "passive"))
      (node (ref "U1") (pin "31") (pinfunction "VSSA_31") (pintype "power_in"))
    )
    (net (code "65") (name "AVDD") (class "Default")
      (node (ref "C5") (pin "1") (pinfunction "1_1") (pintype "passive"))
      (node (ref "FB1") (pin "1") (pinfunction "1_1") (pintype "passive"))
      (node (ref "J6") (pin "3") (pinfunction "3_3") (pintype "passive"))
      (node (ref "U1") (pin "32") (pinfunction "VREF+_32") (pintype "power_in"))
      (node (ref "U1") (pin "33") (pinfunction "VDDA_33") (pintype "power_in"))
    )
    (net (code "66") (name "Chassis_GND") (class "Default")
      (node (ref "J6") (pin "MH1") (pinfunction "MH1_MH1") (pintype "passive"))
      (node (ref "J6") (pin "MH2") (pinfunction "MH2_MH2") (pintype "passive"))
      (node (ref "R16") (pin "1") (pinfunction "1_1") (pintype "passive"))
    )
    (net (code "67") (name "FC_VCC") (class "Default")
      (node (ref "C25") (pin "1") (pinfunction "+_1") (pintype "passive"))
      (node (ref "L1") (pin "1") (pinfunction "1_1") (pintype "passive"))
      (node (ref "R23") (pin "2") (pinfunction "2_2") (pintype "passive"))
      (node (ref "U8") (pin "D1") (pinfunction "BUS_D1") (pintype "passive"))
      (node (ref "U8") (pin "D2") (pinfunction "IN-_D2") (pintype "input"))
    )
    (net (code "68") (name "GND") (class "Default")
      (node (ref "C1") (pin "2") (pinfunction "2_2") (pintype "passive"))
      (node (ref "C10") (pin "2") (pinfunction "2_2") (pintype "passive"))
      (node (ref "C11") (pin "2") (pinfunction "2_2") (pintype "passive"))
      (node (ref "C12") (pin "2") (pinfunction "2_2") (pintype "passive"))
      (node (ref "C13") (pin "2") (pinfunction "2_2") (pintype "passive"))
      (node (ref "C14") (pin "2") (pinfunction "2_2") (pintype "passive"))
      (node (ref "C15") (pin "2") (pinfunction "2_2") (pintype "passive"))
      (node (ref "C16") (pin "2") (pinfunction "2_2") (pintype "passive"))
      (node (ref "C17") (pin "2") (pinfunction "2_2") (pintype "passive"))
      (node (ref "C18") (pin "2") (pinfunction "2_2") (pintype "passive"))
      (node (ref "C2") (pin "2") (pinfunction "2_2") (pintype "passive"))
      (node (ref "C3") (pin "2") (pinfunction "2_2") (pintype "passive"))
      (node (ref "C4") (pin "2") (pinfunction "2_2") (pintype "passive"))
      (node (ref "C48") (pin "1") (pinfunction "C_1") (pintype "passive"))
      (node (ref "C49") (pin "2") (pinfunction "2_2") (pintype "passive"))
      (node (ref "C50") (pin "2") (pinfunction "2_2") (pintype "passive"))
      (node (ref "C52") (pin "2") (pinfunction "2_2") (pintype "passive"))
      (node (ref "C53") (pin "2") (pinfunction "2_2") (pintype "passive"))
      (node (ref "C54") (pin "2") (pinfunction "2_2") (pintype "passive"))
      (node (ref "C55") (pin "2") (pinfunction "2_2") (pintype "passive"))
      (node (ref "C56") (pin "2") (pinfunction "2_2") (pintype "passive"))
      (node (ref "C57") (pin "2") (pinfunction "2_2") (pintype "passive"))
      (node (ref "C6") (pin "2") (pinfunction "2_2") (pintype "passive"))
      (node (ref "C7") (pin "2") (pinfunction "2_2") (pintype "passive"))
      (node (ref "C8") (pin "2") (pinfunction "2_2") (pintype "passive"))
      (node (ref "C9") (pin "2") (pinfunction "2_2") (pintype "passive"))
      (node (ref "J6") (pin "11") (pinfunction "11_11") (pintype "passive"))
      (node (ref "J6") (pin "12") (pinfunction "12_12") (pintype "passive"))
      (node (ref "J6") (pin "15") (pinfunction "15_15") (pintype "passive"))
      (node (ref "J6") (pin "16") (pinfunction "16_16") (pintype "passive"))
      (node (ref "J6") (pin "17") (pinfunction "17_17") (pintype "passive"))
      (node (ref "J6") (pin "22") (pinfunction "22_22") (pintype "passive"))
      (node (ref "J6") (pin "31") (pinfunction "31_31") (pintype "passive"))
      (node (ref "J6") (pin "32") (pinfunction "32_32") (pintype "passive"))
      (node (ref "J6") (pin "37") (pinfunction "37_37") (pintype "passive"))
      (node (ref "J6") (pin "4") (pinfunction "4_4") (pintype "passive"))
      (node (ref "J6") (pin "7") (pinfunction "7_7") (pintype "passive"))
      (node (ref "J6") (pin "8") (pinfunction "8_8") (pintype "passive"))
      (node (ref "J7") (pin "1") (pinfunction "1_1") (pintype "passive"))
      (node (ref "LED1") (pin "1") (pinfunction "K_1") (pintype "passive"))
      (node (ref "LED2") (pin "1") (pinfunction "K_1") (pintype "passive"))
      (node (ref "LED3") (pin "1") (pinfunction "K_1") (pintype "passive"))
      (node (ref "LED4") (pin "1") (pinfunction "K_1") (pintype "passive"))
      (node (ref "P4") (pin "6") (pinfunction "6_6") (pintype "passive"))
      (node (ref "P4") (pin "7") (pinfunction "7_7") (pintype "passive"))
      (node (ref "P6") (pin "1") (pinfunction "1_1") (pintype "passive"))
      (node (ref "P6") (pin "2") (pinfunction "2_2") (pintype "passive"))
      (node (ref "P6") (pin "7") (pinfunction "7_7") (pintype "passive"))
      (node (ref "PS1") (pin "7") (pinfunction "-VOUT_7") (pintype "passive"))
      (node (ref "R10") (pin "1") (pinfunction "1_1") (pintype "passive"))
      (node (ref "R14") (pin "1") (pinfunction "1_1") (pintype "passive"))
      (node (ref "R16") (pin "2") (pinfunction "2_2") (pintype "passive"))
      (node (ref "R17") (pin "1") (pinfunction "1_1") (pintype "passive"))
      (node (ref "R5") (pin "2") (pinfunction "2_2") (pintype "passive"))
      (node (ref "SW1") (pin "3") (pinfunction "3_3") (pintype "passive"))
      (node (ref "SW1") (pin "4") (pinfunction "4_4") (pintype "passive"))
      (node (ref "U1") (pin "107") (pinfunction "VSS_107") (pintype "power_in"))
      (node (ref "U1") (pin "120") (pinfunction "VSS_120") (pintype "power_in"))
      (node (ref "U1") (pin "130") (pinfunction "VSS_130") (pintype "power_in"))
      (node (ref "U1") (pin "143") (pinfunction "PDR_ON_143") (pintype "input"))
      (node (ref "U1") (pin "16") (pinfunction "VSS_16") (pintype "power_in"))
      (node (ref "U1") (pin "38") (pinfunction "VSS_38") (pintype "power_in"))
      (node (ref "U1") (pin "51") (pinfunction "VSS_51") (pintype "power_in"))
      (node (ref "U1") (pin "61") (pinfunction "VSS_61") (pintype "power_in"))
      (node (ref "U1") (pin "83") (pinfunction "VSS_83") (pintype "power_in"))
      (node (ref "U1") (pin "94") (pinfunction "VSS_94") (pintype "power_in"))
      (node (ref "U10") (pin "C1") (pinfunction "GND_C1") (pintype "power_in"))
      (node (ref "U10") (pin "C3") (pinfunction "A1_C3") (pintype "input"))
      (node (ref "U2") (pin "2") (pinfunction "GND_2") (pintype "power_in"))
      (node (ref "U3") (pin "2") (pinfunction "GND_2") (pintype "power_in"))
      (node (ref "U7") (pin "2") (pinfunction "GND_2") (pintype "power_in"))
      (node (ref "U7") (pin "4") (pinfunction "GND_4") (pintype "power_in"))
      (node (ref "U8") (pin "B3") (pinfunction "A0_B3") (pintype "input"))
      (node (ref "U8") (pin "C1") (pinfunction "GND_C1") (pintype "power_in"))
      (node (ref "U8") (pin "C3") (pinfunction "A1_C3") (pintype "input"))
      (node (ref "U9") (pin "C1") (pinfunction "GND_C1") (pintype "power_in"))
      (node (ref "U9") (pin "C3") (pinfunction "A1_C3") (pintype "input"))
      (node (ref "Y1") (pin "2") (pinfunction "GND_2") (pintype "power_in"))
      (node (ref "Y2") (pin "2") (pinfunction "GND_2") (pintype "power_in"))
    )
    (net (code "69") (name "Motor_VCC") (class "Default")
      (node (ref "J4") (pin "P") (pinfunction "P_P") (pintype "power_in"))
      (node (ref "R31") (pin "2") (pinfunction "2_2") (pintype "passive"))
      (node (ref "U10") (pin "D1") (pinfunction "BUS_D1") (pintype "passive"))
      (node (ref "U10") (pin "D2") (pinfunction "IN-_D2") (pintype "input"))
    )
    (net (code "70") (name "Net-(FB1-Pad2)") (class "Default")
      (node (ref "FB1") (pin "2") (pinfunction "2_2") (pintype "passive"))
      (node (ref "R24") (pin "1") (pinfunction "1_1") (pintype "passive"))
    )
    (net (code "71") (name "Net-(LED1-A)") (class "Default")
      (node (ref "LED1") (pin "2") (pinfunction "A_2") (pintype "passive"))
      (node (ref "R2") (pin "2") (pinfunction "2_2") (pintype "passive"))
    )
    (net (code "72") (name "Net-(LED2-A)") (class "Default")
      (node (ref "LED2") (pin "2") (pinfunction "A_2") (pintype "passive"))
      (node (ref "R4") (pin "2") (pinfunction "2_2") (pintype "passive"))
    )
    (net (code "73") (name "Net-(LED3-A)") (class "Default")
      (node (ref "LED3") (pin "2") (pinfunction "A_2") (pintype "passive"))
      (node (ref "R3") (pin "2") (pinfunction "2_2") (pintype "passive"))
    )
    (net (code "74") (name "Net-(LED4-A)") (class "Default")
      (node (ref "LED4") (pin "2") (pinfunction "A_2") (pintype "passive"))
      (node (ref "R6") (pin "2") (pinfunction "2_2") (pintype "passive"))
    )
    (net (code "75") (name "Net-(U1A-PC14-OSC32_IN(PC14))") (class "Default")
      (node (ref "U1") (pin "8") (pinfunction "PC14-OSC32_IN(PC14)_8") (pintype "bidirectional"))
      (node (ref "Y2") (pin "3") (pinfunction "CLK_Out_3") (pintype "output"))
    )
    (net (code "76") (name "Net-(U1B-PH0-OSC_IN(PH0))") (class "Default")
      (node (ref "U1") (pin "23") (pinfunction "PH0-OSC_IN(PH0)_23") (pintype "bidirectional"))
      (node (ref "Y1") (pin "3") (pinfunction "OUT_3") (pintype "passive"))
    )
    (net (code "77") (name "Net-(U1B-VCAP_1)") (class "Default")
      (node (ref "C3") (pin "1") (pinfunction "1_1") (pintype "passive"))
      (node (ref "U1") (pin "71") (pinfunction "VCAP_1_71") (pintype "passive"))
    )
    (net (code "78") (name "Net-(U1B-VCAP_2)") (class "Default")
      (node (ref "C4") (pin "1") (pinfunction "1_1") (pintype "passive"))
      (node (ref "U1") (pin "106") (pinfunction "VCAP_2_106") (pintype "passive"))
    )
    (net (code "79") (name "Net-(U2-S)") (class "Default")
      (node (ref "R10") (pin "2") (pinfunction "2_2") (pintype "passive"))
      (node (ref "U2") (pin "8") (pinfunction "S_8") (pintype "input"))
    )
    (net (code "80") (name "Net-(U3-S)") (class "Default")
      (node (ref "R14") (pin "2") (pinfunction "2_2") (pintype "passive"))
      (node (ref "U3") (pin "8") (pinfunction "S_8") (pintype "input"))
    )
    (net (code "81") (name "Net-(Y1-~{ST})") (class "Default")
      (node (ref "R1") (pin "1") (pinfunction "1_1") (pintype "passive"))
      (node (ref "Y1") (pin "1") (pinfunction "~{ST}_1") (pintype "input"))
    )
    (net (code "82") (name "PA_VCC") (class "Default")
      (node (ref "J2") (pin "P") (pinfunction "P_P") (pintype "power_in"))
      (node (ref "R27") (pin "2") (pinfunction "2_2") (pintype "passive"))
      (node (ref "U9") (pin "D1") (pinfunction "BUS_D1") (pintype "passive"))
      (node (ref "U9") (pin "D2") (pinfunction "IN-_D2") (pintype "input"))
    )
    (net (code "83") (name "VDD_ANA") (class "Default")
      (node (ref "R18") (pin "2") (pinfunction "2_2") (pintype "passive"))
      (node (ref "R19") (pin "2") (pinfunction "2_2") (pintype "passive"))
    )
    (net (code "84") (name "unconnected-(P3-Pad1)") (class "Default")
      (node (ref "P3") (pin "1") (pinfunction "1_1") (pintype "passive+no_connect"))
    )
    (net (code "85") (name "unconnected-(P3-Pad2)") (class "Default")
      (node (ref "P3") (pin "2") (pinfunction "2_2") (pintype "passive+no_connect"))
    )
    (net (code "86") (name "unconnected-(P3-Pad3)") (class "Default")
      (node (ref "P3") (pin "3") (pinfunction "3_3") (pintype "passive+no_connect"))
    )
    (net (code "87") (name "unconnected-(P3-Pad4)") (class "Default")
      (node (ref "P3") (pin "4") (pinfunction "4_4") (pintype "passive+no_connect"))
    )
    (net (code "88") (name "unconnected-(P3-Pad5)") (class "Default")
      (node (ref "P3") (pin "5") (pinfunction "5_5") (pintype "passive+no_connect"))
    )
    (net (code "89") (name "unconnected-(P3-Pad6)") (class "Default")
      (node (ref "P3") (pin "6") (pinfunction "6_6") (pintype "passive+no_connect"))
    )
    (net (code "90") (name "unconnected-(P4-Pad1)") (class "Default")
      (node (ref "P4") (pin "1") (pinfunction "1_1") (pintype "passive+no_connect"))
    )
    (net (code "91") (name "unconnected-(P4-Pad2)") (class "Default")
      (node (ref "P4") (pin "2") (pinfunction "2_2") (pintype "passive+no_connect"))
    )
    (net (code "92") (name "unconnected-(P4-Pad3)") (class "Default")
      (node (ref "P4") (pin "3") (pinfunction "3_3") (pintype "passive+no_connect"))
    )
    (net (code "93") (name "unconnected-(P4-Pad8)") (class "Default")
      (node (ref "P4") (pin "8") (pinfunction "8_8") (pintype "passive+no_connect"))
    )
    (net (code "94") (name "unconnected-(P5-Pad5)") (class "Default")
      (node (ref "P5") (pin "5") (pinfunction "5_5") (pintype "passive+no_connect"))
    )
    (net (code "95") (name "unconnected-(P5-Pad6)") (class "Default")
      (node (ref "P5") (pin "6") (pinfunction "6_6") (pintype "passive+no_connect"))
    )
    (net (code "96") (name "unconnected-(P5-Pad7)") (class "Default")
      (node (ref "P5") (pin "7") (pinfunction "7_7") (pintype "passive+no_connect"))
    )
    (net (code "97") (name "unconnected-(P5-Pad8)") (class "Default")
      (node (ref "P5") (pin "8") (pinfunction "8_8") (pintype "passive+no_connect"))
    )
    (net (code "98") (name "unconnected-(P6-Pad3)") (class "Default")
      (node (ref "P6") (pin "3") (pinfunction "3_3") (pintype "passive+no_connect"))
    )
    (net (code "99") (name "unconnected-(P6-Pad4)") (class "Default")
      (node (ref "P6") (pin "4") (pinfunction "4_4") (pintype "passive+no_connect"))
    )
    (net (code "100") (name "unconnected-(P6-Pad5)") (class "Default")
      (node (ref "P6") (pin "5") (pinfunction "5_5") (pintype "passive+no_connect"))
    )
    (net (code "101") (name "unconnected-(P6-Pad6)") (class "Default")
      (node (ref "P6") (pin "6") (pinfunction "6_6") (pintype "passive+no_connect"))
    )
    (net (code "102") (name "unconnected-(P6-Pad8)") (class "Default")
      (node (ref "P6") (pin "8") (pinfunction "8_8") (pintype "passive+no_connect"))
    )
    (net (code "103") (name "unconnected-(P6-Pad9)") (class "Default")
      (node (ref "P6") (pin "9") (pinfunction "9_9") (pintype "passive+no_connect"))
    )
    (net (code "104") (name "unconnected-(P6-Pad10)") (class "Default")
      (node (ref "P6") (pin "10") (pinfunction "10_10") (pintype "passive+no_connect"))
    )
    (net (code "105") (name "unconnected-(PS1-CTRL-Pad3)") (class "Default")
      (node (ref "PS1") (pin "3") (pinfunction "CTRL_3") (pintype "passive+no_connect"))
    )
    (net (code "106") (name "unconnected-(PS1-NC-Pad8)") (class "Default")
      (node (ref "PS1") (pin "8") (pinfunction "NC_8") (pintype "passive+no_connect"))
    )
    (net (code "107") (name "unconnected-(PS1-TRIM-Pad5)") (class "Default")
      (node (ref "PS1") (pin "5") (pinfunction "TRIM_5") (pintype "passive+no_connect"))
    )
    (net (code "108") (name "unconnected-(U1A-PA8-Pad100)") (class "Default")
      (node (ref "U1") (pin "100") (pinfunction "PA8_100") (pintype "bidirectional+no_connect"))
    )
    (net (code "109") (name "unconnected-(U1A-PB1-Pad47)") (class "Default")
      (node (ref "U1") (pin "47") (pinfunction "PB1_47") (pintype "bidirectional+no_connect"))
    )
    (net (code "110") (name "unconnected-(U1A-PB2-BOOT1(PB2)-Pad48)") (class "Default")
      (node (ref "U1") (pin "48") (pinfunction "PB2-BOOT1(PB2)_48") (pintype "bidirectional+no_connect"))
    )
    (net (code "111") (name "unconnected-(U1A-PB4(NJTRST)-Pad134)") (class "Default")
      (node (ref "U1") (pin "134") (pinfunction "PB4(NJTRST)_134") (pintype "bidirectional+no_connect"))
    )
    (net (code "112") (name "unconnected-(U1A-PB5-Pad135)") (class "Default")
      (node (ref "U1") (pin "135") (pinfunction "PB5_135") (pintype "bidirectional+no_connect"))
    )
    (net (code "113") (name "unconnected-(U1A-PB6-Pad136)") (class "Default")
      (node (ref "U1") (pin "136") (pinfunction "PB6_136") (pintype "bidirectional+no_connect"))
    )
    (net (code "114") (name "unconnected-(U1A-PB7-Pad137)") (class "Default")
      (node (ref "U1") (pin "137") (pinfunction "PB7_137") (pintype "bidirectional+no_connect"))
    )
    (net (code "115") (name "unconnected-(U1A-PB8-Pad139)") (class "Default")
      (node (ref "U1") (pin "139") (pinfunction "PB8_139") (pintype "bidirectional+no_connect"))
    )
    (net (code "116") (name "unconnected-(U1A-PB14-Pad75)") (class "Default")
      (node (ref "U1") (pin "75") (pinfunction "PB14_75") (pintype "bidirectional+no_connect"))
    )
    (net (code "117") (name "unconnected-(U1A-PB15-Pad76)") (class "Default")
      (node (ref "U1") (pin "76") (pinfunction "PB15_76") (pintype "bidirectional+no_connect"))
    )
    (net (code "118") (name "unconnected-(U1A-PC0-Pad26)") (class "Default")
      (node (ref "U1") (pin "26") (pinfunction "PC0_26") (pintype "bidirectional+no_connect"))
    )
    (net (code "119") (name "unconnected-(U1A-PC8-Pad98)") (class "Default")
      (node (ref "U1") (pin "98") (pinfunction "PC8_98") (pintype "bidirectional+no_connect"))
    )
    (net (code "120") (name "unconnected-(U1A-PC9-Pad99)") (class "Default")
      (node (ref "U1") (pin "99") (pinfunction "PC9_99") (pintype "bidirectional+no_connect"))
    )
    (net (code "121") (name "unconnected-(U1A-PC13-Pad7)") (class "Default")
      (node (ref "U1") (pin "7") (pinfunction "PC13_7") (pintype "bidirectional+no_connect"))
    )
    (net (code "122") (name "unconnected-(U1A-PC15-OSC32_OUT(PC15)-Pad9)") (class "Default")
      (node (ref "U1") (pin "9") (pinfunction "PC15-OSC32_OUT(PC15)_9") (pintype "bidirectional+no_connect"))
    )
    (net (code "123") (name "unconnected-(U1A-PD0-Pad114)") (class "Default")
      (node (ref "U1") (pin "114") (pinfunction "PD0_114") (pintype "bidirectional+no_connect"))
    )
    (net (code "124") (name "unconnected-(U1A-PD1-Pad115)") (class "Default")
      (node (ref "U1") (pin "115") (pinfunction "PD1_115") (pintype "bidirectional+no_connect"))
    )
    (net (code "125") (name "unconnected-(U1A-PD2-Pad116)") (class "Default")
      (node (ref "U1") (pin "116") (pinfunction "PD2_116") (pintype "bidirectional+no_connect"))
    )
    (net (code "126") (name "unconnected-(U1A-PD3-Pad117)") (class "Default")
      (node (ref "U1") (pin "117") (pinfunction "PD3_117") (pintype "bidirectional+no_connect"))
    )
    (net (code "127") (name "unconnected-(U1A-PD4-Pad118)") (class "Default")
      (node (ref "U1") (pin "118") (pinfunction "PD4_118") (pintype "bidirectional+no_connect"))
    )
    (net (code "128") (name "unconnected-(U1A-PD5-Pad119)") (class "Default")
      (node (ref "U1") (pin "119") (pinfunction "PD5_119") (pintype "bidirectional+no_connect"))
    )
    (net (code "129") (name "unconnected-(U1A-PD6-Pad122)") (class "Default")
      (node (ref "U1") (pin "122") (pinfunction "PD6_122") (pintype "bidirectional+no_connect"))
    )
    (net (code "130") (name "unconnected-(U1A-PD7-Pad123)") (class "Default")
      (node (ref "U1") (pin "123") (pinfunction "PD7_123") (pintype "bidirectional+no_connect"))
    )
    (net (code "131") (name "unconnected-(U1A-PD8-Pad77)") (class "Default")
      (node (ref "U1") (pin "77") (pinfunction "PD8_77") (pintype "bidirectional+no_connect"))
    )
    (net (code "132") (name "unconnected-(U1A-PD9-Pad78)") (class "Default")
      (node (ref "U1") (pin "78") (pinfunction "PD9_78") (pintype "bidirectional+no_connect"))
    )
    (net (code "133") (name "unconnected-(U1A-PD10-Pad79)") (class "Default")
      (node (ref "U1") (pin "79") (pinfunction "PD10_79") (pintype "bidirectional+no_connect"))
    )
    (net (code "134") (name "unconnected-(U1A-PD11-Pad80)") (class "Default")
      (node (ref "U1") (pin "80") (pinfunction "PD11_80") (pintype "bidirectional+no_connect"))
    )
    (net (code "135") (name "unconnected-(U1A-PD12-Pad81)") (class "Default")
      (node (ref "U1") (pin "81") (pinfunction "PD12_81") (pintype "bidirectional+no_connect"))
    )
    (net (code "136") (name "unconnected-(U1A-PD13-Pad82)") (class "Default")
      (node (ref "U1") (pin "82") (pinfunction "PD13_82") (pintype "bidirectional+no_connect"))
    )
    (net (code "137") (name "unconnected-(U1A-PD14-Pad85)") (class "Default")
      (node (ref "U1") (pin "85") (pinfunction "PD14_85") (pintype "bidirectional+no_connect"))
    )
    (net (code "138") (name "unconnected-(U1A-PD15-Pad86)") (class "Default")
      (node (ref "U1") (pin "86") (pinfunction "PD15_86") (pintype "bidirectional+no_connect"))
    )
    (net (code "139") (name "unconnected-(U1A-PE3-Pad2)") (class "Default")
      (node (ref "U1") (pin "2") (pinfunction "PE3_2") (pintype "bidirectional+no_connect"))
    )
    (net (code "140") (name "unconnected-(U1A-PE7-Pad58)") (class "Default")
      (node (ref "U1") (pin "58") (pinfunction "PE7_58") (pintype "bidirectional+no_connect"))
    )
    (net (code "141") (name "unconnected-(U1A-PE8-Pad59)") (class "Default")
      (node (ref "U1") (pin "59") (pinfunction "PE8_59") (pintype "bidirectional+no_connect"))
    )
    (net (code "142") (name "unconnected-(U1A-PE9-Pad60)") (class "Default")
      (node (ref "U1") (pin "60") (pinfunction "PE9_60") (pintype "bidirectional+no_connect"))
    )
    (net (code "143") (name "unconnected-(U1A-PE10-Pad63)") (class "Default")
      (node (ref "U1") (pin "63") (pinfunction "PE10_63") (pintype "bidirectional+no_connect"))
    )
    (net (code "144") (name "unconnected-(U1A-PE11-Pad64)") (class "Default")
      (node (ref "U1") (pin "64") (pinfunction "PE11_64") (pintype "bidirectional+no_connect"))
    )
    (net (code "145") (name "unconnected-(U1A-PE12-Pad65)") (class "Default")
      (node (ref "U1") (pin "65") (pinfunction "PE12_65") (pintype "bidirectional+no_connect"))
    )
    (net (code "146") (name "unconnected-(U1A-PF0-Pad10)") (class "Default")
      (node (ref "U1") (pin "10") (pinfunction "PF0_10") (pintype "bidirectional+no_connect"))
    )
    (net (code "147") (name "unconnected-(U1A-PF1-Pad11)") (class "Default")
      (node (ref "U1") (pin "11") (pinfunction "PF1_11") (pintype "bidirectional+no_connect"))
    )
    (net (code "148") (name "unconnected-(U1A-PF2-Pad12)") (class "Default")
      (node (ref "U1") (pin "12") (pinfunction "PF2_12") (pintype "bidirectional+no_connect"))
    )
    (net (code "149") (name "unconnected-(U1A-PF3-Pad13)") (class "Default")
      (node (ref "U1") (pin "13") (pinfunction "PF3_13") (pintype "bidirectional+no_connect"))
    )
    (net (code "150") (name "unconnected-(U1A-PF4-Pad14)") (class "Default")
      (node (ref "U1") (pin "14") (pinfunction "PF4_14") (pintype "bidirectional+no_connect"))
    )
    (net (code "151") (name "unconnected-(U1A-PF5-Pad15)") (class "Default")
      (node (ref "U1") (pin "15") (pinfunction "PF5_15") (pintype "bidirectional+no_connect"))
    )
    (net (code "152") (name "unconnected-(U1A-PF6-Pad18)") (class "Default")
      (node (ref "U1") (pin "18") (pinfunction "PF6_18") (pintype "bidirectional+no_connect"))
    )
    (net (code "153") (name "unconnected-(U1A-PF7-Pad19)") (class "Default")
      (node (ref "U1") (pin "19") (pinfunction "PF7_19") (pintype "bidirectional+no_connect"))
    )
    (net (code "154") (name "unconnected-(U1A-PF8-Pad20)") (class "Default")
      (node (ref "U1") (pin "20") (pinfunction "PF8_20") (pintype "bidirectional+no_connect"))
    )
    (net (code "155") (name "unconnected-(U1A-PF9-Pad21)") (class "Default")
      (node (ref "U1") (pin "21") (pinfunction "PF9_21") (pintype "bidirectional+no_connect"))
    )
    (net (code "156") (name "unconnected-(U1A-PF10-Pad22)") (class "Default")
      (node (ref "U1") (pin "22") (pinfunction "PF10_22") (pintype "bidirectional+no_connect"))
    )
    (net (code "157") (name "unconnected-(U1A-PF11-Pad49)") (class "Default")
      (node (ref "U1") (pin "49") (pinfunction "PF11_49") (pintype "bidirectional+no_connect"))
    )
    (net (code "158") (name "unconnected-(U1A-PF12-Pad50)") (class "Default")
      (node (ref "U1") (pin "50") (pinfunction "PF12_50") (pintype "bidirectional+no_connect"))
    )
    (net (code "159") (name "unconnected-(U1A-PF13-Pad53)") (class "Default")
      (node (ref "U1") (pin "53") (pinfunction "PF13_53") (pintype "bidirectional+no_connect"))
    )
    (net (code "160") (name "unconnected-(U1A-PF14-Pad54)") (class "Default")
      (node (ref "U1") (pin "54") (pinfunction "PF14_54") (pintype "bidirectional+no_connect"))
    )
    (net (code "161") (name "unconnected-(U1A-PF15-Pad55)") (class "Default")
      (node (ref "U1") (pin "55") (pinfunction "PF15_55") (pintype "bidirectional+no_connect"))
    )
    (net (code "162") (name "unconnected-(U1B-PG0-Pad56)") (class "Default")
      (node (ref "U1") (pin "56") (pinfunction "PG0_56") (pintype "bidirectional+no_connect"))
    )
    (net (code "163") (name "unconnected-(U1B-PG1-Pad57)") (class "Default")
      (node (ref "U1") (pin "57") (pinfunction "PG1_57") (pintype "bidirectional+no_connect"))
    )
    (net (code "164") (name "unconnected-(U1B-PG6-Pad91)") (class "Default")
      (node (ref "U1") (pin "91") (pinfunction "PG6_91") (pintype "bidirectional+no_connect"))
    )
    (net (code "165") (name "unconnected-(U1B-PG7-Pad92)") (class "Default")
      (node (ref "U1") (pin "92") (pinfunction "PG7_92") (pintype "bidirectional+no_connect"))
    )
    (net (code "166") (name "unconnected-(U1B-PG8-Pad93)") (class "Default")
      (node (ref "U1") (pin "93") (pinfunction "PG8_93") (pintype "bidirectional+no_connect"))
    )
    (net (code "167") (name "unconnected-(U1B-PG12-Pad127)") (class "Default")
      (node (ref "U1") (pin "127") (pinfunction "PG12_127") (pintype "bidirectional+no_connect"))
    )
    (net (code "168") (name "unconnected-(U1B-PG13-Pad128)") (class "Default")
      (node (ref "U1") (pin "128") (pinfunction "PG13_128") (pintype "bidirectional+no_connect"))
    )
    (net (code "169") (name "unconnected-(U1B-PG14-Pad129)") (class "Default")
      (node (ref "U1") (pin "129") (pinfunction "PG14_129") (pintype "bidirectional+no_connect"))
    )
    (net (code "170") (name "unconnected-(U1B-PG15-Pad132)") (class "Default")
      (node (ref "U1") (pin "132") (pinfunction "PG15_132") (pintype "bidirectional+no_connect"))
    )
    (net (code "171") (name "unconnected-(U1B-PH1-OSC_OUT(PH1)-Pad24)") (class "Default")
      (node (ref "U1") (pin "24") (pinfunction "PH1-OSC_OUT(PH1)_24") (pintype "bidirectional+no_connect"))
    )
    (net (code "172") (name "unconnected-(U2-VREF-Pad5)") (class "Default")
      (node (ref "U2") (pin "5") (pinfunction "VREF_5") (pintype "output+no_connect"))
    )
    (net (code "173") (name "unconnected-(U3-VREF-Pad5)") (class "Default")
      (node (ref "U3") (pin "5") (pinfunction "VREF_5") (pintype "output+no_connect"))
    )
    (net (code "174") (name "unconnected-(U8-NC-PadB2)") (class "Default")
      (node (ref "U8") (pin "B2") (pinfunction "NC_B2") (pintype "passive+no_connect"))
    )
    (net (code "175") (name "unconnected-(U8-NC-PadC2)") (class "Default")
      (node (ref "U8") (pin "C2") (pinfunction "NC_C2") (pintype "passive+no_connect"))
    )
    (net (code "176") (name "unconnected-(U9-NC-PadB2)") (class "Default")
      (node (ref "U9") (pin "B2") (pinfunction "NC_B2") (pintype "passive+no_connect"))
    )
    (net (code "177") (name "unconnected-(U9-NC-PadC2)") (class "Default")
      (node (ref "U9") (pin "C2") (pinfunction "NC_C2") (pintype "passive+no_connect"))
    )
    (net (code "178") (name "unconnected-(U10-NC-PadB2)") (class "Default")
      (node (ref "U10") (pin "B2") (pinfunction "NC_B2") (pintype "passive+no_connect"))
    )
    (net (code "179") (name "unconnected-(U10-NC-PadC2)") (class "Default")
      (node (ref "U10") (pin "C2") (pinfunction "NC_C2") (pintype "passive+no_connect"))
    )
    (net (code "180") (name "unconnected-(Y2-NC-Pad1)") (class "Default")
      (node (ref "Y2") (pin "1") (pinfunction "NC_1") (pintype "passive+no_connect"))
    )
  )
)
